# GNSS_B.net
KiCad netlist of a schematic drawn in Altium Designer
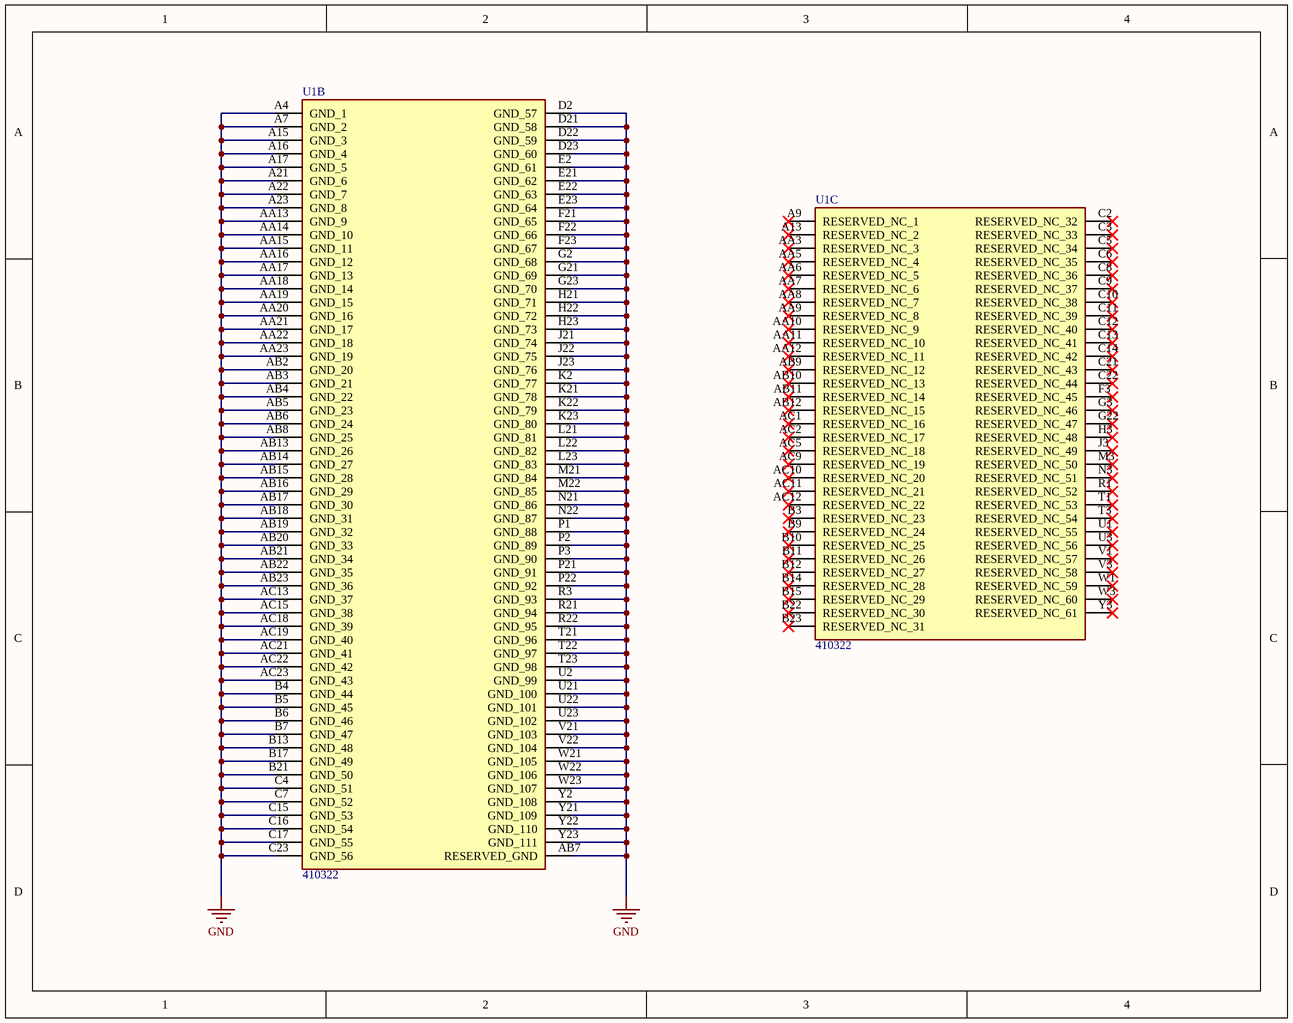
[diagram p0: GNSS_B.SchDoc]

(export (version "E")
  (design (tool "Eeschema 10.0.6"))
  (components
    (comp (ref "U1")
      (value "410322")
      (footprint "LGA239C127P23X23_3100X3100X417N")
      (description "mosaicâ„¢-X5 RF Receiver BeiDou, Galileo, GLONASS, GNSS, GPS")
      (fields (field (name "MF") "Septentrio Inc."))
      (libsource (lib "410322") (part "410322"))
    )
  )
  (nets
    (net (code "1") (name "GND") (class "Default")
      (node (ref "U1") (pin "A15") (pinfunction "GND_3_A15") (pintype "power_in"))
      (node (ref "U1") (pin "A16") (pinfunction "GND_4_A16") (pintype "power_in"))
      (node (ref "U1") (pin "A17") (pinfunction "GND_5_A17") (pintype "power_in"))
      (node (ref "U1") (pin "A21") (pinfunction "GND_6_A21") (pintype "power_in"))
      (node (ref "U1") (pin "A22") (pinfunction "GND_7_A22") (pintype "power_in"))
      (node (ref "U1") (pin "A23") (pinfunction "GND_8_A23") (pintype "power_in"))
      (node (ref "U1") (pin "A4") (pinfunction "GND_1_A4") (pintype "power_in"))
      (node (ref "U1") (pin "A7") (pinfunction "GND_2_A7") (pintype "power_in"))
      (node (ref "U1") (pin "AA13") (pinfunction "GND_9_AA13") (pintype "power_in"))
      (node (ref "U1") (pin "AA14") (pinfunction "GND_10_AA14") (pintype "power_in"))
      (node (ref "U1") (pin "AA15") (pinfunction "GND_11_AA15") (pintype "power_in"))
      (node (ref "U1") (pin "AA16") (pinfunction "GND_12_AA16") (pintype "power_in"))
      (node (ref "U1") (pin "AA17") (pinfunction "GND_13_AA17") (pintype "power_in"))
      (node (ref "U1") (pin "AA18") (pinfunction "GND_14_AA18") (pintype "power_in"))
      (node (ref "U1") (pin "AA19") (pinfunction "GND_15_AA19") (pintype "power_in"))
      (node (ref "U1") (pin "AA20") (pinfunction "GND_16_AA20") (pintype "power_in"))
      (node (ref "U1") (pin "AA21") (pinfunction "GND_17_AA21") (pintype "power_in"))
      (node (ref "U1") (pin "AA22") (pinfunction "GND_18_AA22") (pintype "power_in"))
      (node (ref "U1") (pin "AA23") (pinfunction "GND_19_AA23") (pintype "power_in"))
      (node (ref "U1") (pin "AB13") (pinfunction "GND_26_AB13") (pintype "power_in"))
      (node (ref "U1") (pin "AB14") (pinfunction "GND_27_AB14") (pintype "power_in"))
      (node (ref "U1") (pin "AB15") (pinfunction "GND_28_AB15") (pintype "power_in"))
      (node (ref "U1") (pin "AB16") (pinfunction "GND_29_AB16") (pintype "power_in"))
      (node (ref "U1") (pin "AB17") (pinfunction "GND_30_AB17") (pintype "power_in"))
      (node (ref "U1") (pin "AB18") (pinfunction "GND_31_AB18") (pintype "power_in"))
      (node (ref "U1") (pin "AB19") (pinfunction "GND_32_AB19") (pintype "power_in"))
      (node (ref "U1") (pin "AB2") (pinfunction "GND_20_AB2") (pintype "power_in"))
      (node (ref "U1") (pin "AB20") (pinfunction "GND_33_AB20") (pintype "power_in"))
      (node (ref "U1") (pin "AB21") (pinfunction "GND_34_AB21") (pintype "power_in"))
      (node (ref "U1") (pin "AB22") (pinfunction "GND_35_AB22") (pintype "power_in"))
      (node (ref "U1") (pin "AB23") (pinfunction "GND_36_AB23") (pintype "power_in"))
      (node (ref "U1") (pin "AB3") (pinfunction "GND_21_AB3") (pintype "power_in"))
      (node (ref "U1") (pin "AB4") (pinfunction "GND_22_AB4") (pintype "power_in"))
      (node (ref "U1") (pin "AB5") (pinfunction "GND_23_AB5") (pintype "power_in"))
      (node (ref "U1") (pin "AB6") (pinfunction "GND_24_AB6") (pintype "power_in"))
      (node (ref "U1") (pin "AB7") (pinfunction "RESERVED_GND_AB7") (pintype "passive"))
      (node (ref "U1") (pin "AB8") (pinfunction "GND_25_AB8") (pintype "power_in"))
      (node (ref "U1") (pin "AC13") (pinfunction "GND_37_AC13") (pintype "power_in"))
      (node (ref "U1") (pin "AC15") (pinfunction "GND_38_AC15") (pintype "power_in"))
      (node (ref "U1") (pin "AC18") (pinfunction "GND_39_AC18") (pintype "power_in"))
      (node (ref "U1") (pin "AC19") (pinfunction "GND_40_AC19") (pintype "power_in"))
      (node (ref "U1") (pin "AC21") (pinfunction "GND_41_AC21") (pintype "power_in"))
      (node (ref "U1") (pin "AC22") (pinfunction "GND_42_AC22") (pintype "power_in"))
      (node (ref "U1") (pin "AC23") (pinfunction "GND_43_AC23") (pintype "power_in"))
      (node (ref "U1") (pin "B13") (pinfunction "GND_48_B13") (pintype "power_in"))
      (node (ref "U1") (pin "B17") (pinfunction "GND_49_B17") (pintype "power_in"))
      (node (ref "U1") (pin "B21") (pinfunction "GND_50_B21") (pintype "power_in"))
      (node (ref "U1") (pin "B4") (pinfunction "GND_44_B4") (pintype "power_in"))
      (node (ref "U1") (pin "B5") (pinfunction "GND_45_B5") (pintype "power_in"))
      (node (ref "U1") (pin "B6") (pinfunction "GND_46_B6") (pintype "power_in"))
      (node (ref "U1") (pin "B7") (pinfunction "GND_47_B7") (pintype "power_in"))
      (node (ref "U1") (pin "C15") (pinfunction "GND_53_C15") (pintype "power_in"))
      (node (ref "U1") (pin "C16") (pinfunction "GND_54_C16") (pintype "power_in"))
      (node (ref "U1") (pin "C17") (pinfunction "GND_55_C17") (pintype "power_in"))
      (node (ref "U1") (pin "C23") (pinfunction "GND_56_C23") (pintype "power_in"))
      (node (ref "U1") (pin "C4") (pinfunction "GND_51_C4") (pintype "power_in"))
      (node (ref "U1") (pin "C7") (pinfunction "GND_52_C7") (pintype "power_in"))
      (node (ref "U1") (pin "D2") (pinfunction "GND_57_D2") (pintype "power_in"))
      (node (ref "U1") (pin "D21") (pinfunction "GND_58_D21") (pintype "power_in"))
      (node (ref "U1") (pin "D22") (pinfunction "GND_59_D22") (pintype "power_in"))
      (node (ref "U1") (pin "D23") (pinfunction "GND_60_D23") (pintype "power_in"))
      (node (ref "U1") (pin "E2") (pinfunction "GND_61_E2") (pintype "power_in"))
      (node (ref "U1") (pin "E21") (pinfunction "GND_62_E21") (pintype "power_in"))
      (node (ref "U1") (pin "E22") (pinfunction "GND_63_E22") (pintype "power_in"))
      (node (ref "U1") (pin "E23") (pinfunction "GND_64_E23") (pintype "power_in"))
      (node (ref "U1") (pin "F21") (pinfunction "GND_65_F21") (pintype "power_in"))
      (node (ref "U1") (pin "F22") (pinfunction "GND_66_F22") (pintype "power_in"))
      (node (ref "U1") (pin "F23") (pinfunction "GND_67_F23") (pintype "power_in"))
      (node (ref "U1") (pin "G2") (pinfunction "GND_68_G2") (pintype "power_in"))
      (node (ref "U1") (pin "G21") (pinfunction "GND_69_G21") (pintype "power_in"))
      (node (ref "U1") (pin "G23") (pinfunction "GND_70_G23") (pintype "power_in"))
      (node (ref "U1") (pin "H21") (pinfunction "GND_71_H21") (pintype "power_in"))
      (node (ref "U1") (pin "H22") (pinfunction "GND_72_H22") (pintype "power_in"))
      (node (ref "U1") (pin "H23") (pinfunction "GND_73_H23") (pintype "power_in"))
      (node (ref "U1") (pin "J21") (pinfunction "GND_74_J21") (pintype "power_in"))
      (node (ref "U1") (pin "J22") (pinfunction "GND_75_J22") (pintype "power_in"))
      (node (ref "U1") (pin "J23") (pinfunction "GND_76_J23") (pintype "power_in"))
      (node (ref "U1") (pin "K2") (pinfunction "GND_77_K2") (pintype "power_in"))
      (node (ref "U1") (pin "K21") (pinfunction "GND_78_K21") (pintype "power_in"))
      (node (ref "U1") (pin "K22") (pinfunction "GND_79_K22") (pintype "power_in"))
      (node (ref "U1") (pin "K23") (pinfunction "GND_80_K23") (pintype "power_in"))
      (node (ref "U1") (pin "L21") (pinfunction "GND_81_L21") (pintype "power_in"))
      (node (ref "U1") (pin "L22") (pinfunction "GND_82_L22") (pintype "power_in"))
      (node (ref "U1") (pin "L23") (pinfunction "GND_83_L23") (pintype "power_in"))
      (node (ref "U1") (pin "M21") (pinfunction "GND_84_M21") (pintype "power_in"))
      (node (ref "U1") (pin "M22") (pinfunction "GND_85_M22") (pintype "power_in"))
      (node (ref "U1") (pin "N21") (pinfunction "GND_86_N21") (pintype "power_in"))
      (node (ref "U1") (pin "N22") (pinfunction "GND_87_N22") (pintype "power_in"))
      (node (ref "U1") (pin "P1") (pinfunction "GND_88_P1") (pintype "power_in"))
      (node (ref "U1") (pin "P2") (pinfunction "GND_89_P2") (pintype "power_in"))
      (node (ref "U1") (pin "P21") (pinfunction "GND_91_P21") (pintype "power_in"))
      (node (ref "U1") (pin "P22") (pinfunction "GND_92_P22") (pintype "power_in"))
      (node (ref "U1") (pin "P3") (pinfunction "GND_90_P3") (pintype "power_in"))
      (node (ref "U1") (pin "R21") (pinfunction "GND_94_R21") (pintype "power_in"))
      (node (ref "U1") (pin "R22") (pinfunction "GND_95_R22") (pintype "power_in"))
      (node (ref "U1") (pin "R3") (pinfunction "GND_93_R3") (pintype "power_in"))
      (node (ref "U1") (pin "T21") (pinfunction "GND_96_T21") (pintype "power_in"))
      (node (ref "U1") (pin "T22") (pinfunction "GND_97_T22") (pintype "power_in"))
      (node (ref "U1") (pin "T23") (pinfunction "GND_98_T23") (pintype "power_in"))
      (node (ref "U1") (pin "U2") (pinfunction "GND_99_U2") (pintype "power_in"))
      (node (ref "U1") (pin "U21") (pinfunction "GND_100_U21") (pintype "power_in"))
      (node (ref "U1") (pin "U22") (pinfunction "GND_101_U22") (pintype "power_in"))
      (node (ref "U1") (pin "U23") (pinfunction "GND_102_U23") (pintype "power_in"))
      (node (ref "U1") (pin "V21") (pinfunction "GND_103_V21") (pintype "power_in"))
      (node (ref "U1") (pin "V22") (pinfunction "GND_104_V22") (pintype "power_in"))
      (node (ref "U1") (pin "W21") (pinfunction "GND_105_W21") (pintype "power_in"))
      (node (ref "U1") (pin "W22") (pinfunction "GND_106_W22") (pintype "power_in"))
      (node (ref "U1") (pin "W23") (pinfunction "GND_107_W23") (pintype "power_in"))
      (node (ref "U1") (pin "Y2") (pinfunction "GND_108_Y2") (pintype "power_in"))
      (node (ref "U1") (pin "Y21") (pinfunction "GND_109_Y21") (pintype "power_in"))
      (node (ref "U1") (pin "Y22") (pinfunction "GND_110_Y22") (pintype "power_in"))
      (node (ref "U1") (pin "Y23") (pinfunction "GND_111_Y23") (pintype "power_in"))
    )
    (net (code "2") (name "unconnected-(U1C-RESERVED_NC_1-PadA9)") (class "Default")
      (node (ref "U1") (pin "A9") (pinfunction "RESERVED_NC_1_A9") (pintype "passive+no_connect"))
    )
    (net (code "3") (name "unconnected-(U1C-RESERVED_NC_2-PadA13)") (class "Default")
      (node (ref "U1") (pin "A13") (pinfunction "RESERVED_NC_2_A13") (pintype "passive+no_connect"))
    )
    (net (code "4") (name "unconnected-(U1C-RESERVED_NC_3-PadAA3)") (class "Default")
      (node (ref "U1") (pin "AA3") (pinfunction "RESERVED_NC_3_AA3") (pintype "passive+no_connect"))
    )
    (net (code "5") (name "unconnected-(U1C-RESERVED_NC_4-PadAA5)") (class "Default")
      (node (ref "U1") (pin "AA5") (pinfunction "RESERVED_NC_4_AA5") (pintype "passive+no_connect"))
    )
    (net (code "6") (name "unconnected-(U1C-RESERVED_NC_5-PadAA6)") (class "Default")
      (node (ref "U1") (pin "AA6") (pinfunction "RESERVED_NC_5_AA6") (pintype "passive+no_connect"))
    )
    (net (code "7") (name "unconnected-(U1C-RESERVED_NC_6-PadAA7)") (class "Default")
      (node (ref "U1") (pin "AA7") (pinfunction "RESERVED_NC_6_AA7") (pintype "passive+no_connect"))
    )
    (net (code "8") (name "unconnected-(U1C-RESERVED_NC_7-PadAA8)") (class "Default")
      (node (ref "U1") (pin "AA8") (pinfunction "RESERVED_NC_7_AA8") (pintype "passive+no_connect"))
    )
    (net (code "9") (name "unconnected-(U1C-RESERVED_NC_8-PadAA9)") (class "Default")
      (node (ref "U1") (pin "AA9") (pinfunction "RESERVED_NC_8_AA9") (pintype "passive+no_connect"))
    )
    (net (code "10") (name "unconnected-(U1C-RESERVED_NC_9-PadAA10)") (class "Default")
      (node (ref "U1") (pin "AA10") (pinfunction "RESERVED_NC_9_AA10") (pintype "passive+no_connect"))
    )
    (net (code "11") (name "unconnected-(U1C-RESERVED_NC_10-PadAA11)") (class "Default")
      (node (ref "U1") (pin "AA11") (pinfunction "RESERVED_NC_10_AA11") (pintype "passive+no_connect"))
    )
    (net (code "12") (name "unconnected-(U1C-RESERVED_NC_11-PadAA12)") (class "Default")
      (node (ref "U1") (pin "AA12") (pinfunction "RESERVED_NC_11_AA12") (pintype "passive+no_connect"))
    )
    (net (code "13") (name "unconnected-(U1C-RESERVED_NC_12-PadAB9)") (class "Default")
      (node (ref "U1") (pin "AB9") (pinfunction "RESERVED_NC_12_AB9") (pintype "passive+no_connect"))
    )
    (net (code "14") (name "unconnected-(U1C-RESERVED_NC_13-PadAB10)") (class "Default")
      (node (ref "U1") (pin "AB10") (pinfunction "RESERVED_NC_13_AB10") (pintype "passive+no_connect"))
    )
    (net (code "15") (name "unconnected-(U1C-RESERVED_NC_14-PadAB11)") (class "Default")
      (node (ref "U1") (pin "AB11") (pinfunction "RESERVED_NC_14_AB11") (pintype "passive+no_connect"))
    )
    (net (code "16") (name "unconnected-(U1C-RESERVED_NC_15-PadAB12)") (class "Default")
      (node (ref "U1") (pin "AB12") (pinfunction "RESERVED_NC_15_AB12") (pintype "passive+no_connect"))
    )
    (net (code "17") (name "unconnected-(U1C-RESERVED_NC_16-PadAC1)") (class "Default")
      (node (ref "U1") (pin "AC1") (pinfunction "RESERVED_NC_16_AC1") (pintype "passive+no_connect"))
    )
    (net (code "18") (name "unconnected-(U1C-RESERVED_NC_17-PadAC2)") (class "Default")
      (node (ref "U1") (pin "AC2") (pinfunction "RESERVED_NC_17_AC2") (pintype "passive+no_connect"))
    )
    (net (code "19") (name "unconnected-(U1C-RESERVED_NC_18-PadAC5)") (class "Default")
      (node (ref "U1") (pin "AC5") (pinfunction "RESERVED_NC_18_AC5") (pintype "passive+no_connect"))
    )
    (net (code "20") (name "unconnected-(U1C-RESERVED_NC_19-PadAC9)") (class "Default")
      (node (ref "U1") (pin "AC9") (pinfunction "RESERVED_NC_19_AC9") (pintype "passive+no_connect"))
    )
    (net (code "21") (name "unconnected-(U1C-RESERVED_NC_20-PadAC10)") (class "Default")
      (node (ref "U1") (pin "AC10") (pinfunction "RESERVED_NC_20_AC10") (pintype "passive+no_connect"))
    )
    (net (code "22") (name "unconnected-(U1C-RESERVED_NC_21-PadAC11)") (class "Default")
      (node (ref "U1") (pin "AC11") (pinfunction "RESERVED_NC_21_AC11") (pintype "passive+no_connect"))
    )
    (net (code "23") (name "unconnected-(U1C-RESERVED_NC_22-PadAC12)") (class "Default")
      (node (ref "U1") (pin "AC12") (pinfunction "RESERVED_NC_22_AC12") (pintype "passive+no_connect"))
    )
    (net (code "24") (name "unconnected-(U1C-RESERVED_NC_23-PadB3)") (class "Default")
      (node (ref "U1") (pin "B3") (pinfunction "RESERVED_NC_23_B3") (pintype "passive+no_connect"))
    )
    (net (code "25") (name "unconnected-(U1C-RESERVED_NC_24-PadB9)") (class "Default")
      (node (ref "U1") (pin "B9") (pinfunction "RESERVED_NC_24_B9") (pintype "passive+no_connect"))
    )
    (net (code "26") (name "unconnected-(U1C-RESERVED_NC_25-PadB10)") (class "Default")
      (node (ref "U1") (pin "B10") (pinfunction "RESERVED_NC_25_B10") (pintype "passive+no_connect"))
    )
    (net (code "27") (name "unconnected-(U1C-RESERVED_NC_26-PadB11)") (class "Default")
      (node (ref "U1") (pin "B11") (pinfunction "RESERVED_NC_26_B11") (pintype "passive+no_connect"))
    )
    (net (code "28") (name "unconnected-(U1C-RESERVED_NC_27-PadB12)") (class "Default")
      (node (ref "U1") (pin "B12") (pinfunction "RESERVED_NC_27_B12") (pintype "passive+no_connect"))
    )
    (net (code "29") (name "unconnected-(U1C-RESERVED_NC_28-PadB14)") (class "Default")
      (node (ref "U1") (pin "B14") (pinfunction "RESERVED_NC_28_B14") (pintype "passive+no_connect"))
    )
    (net (code "30") (name "unconnected-(U1C-RESERVED_NC_29-PadB15)") (class "Default")
      (node (ref "U1") (pin "B15") (pinfunction "RESERVED_NC_29_B15") (pintype "passive+no_connect"))
    )
    (net (code "31") (name "unconnected-(U1C-RESERVED_NC_30-PadB22)") (class "Default")
      (node (ref "U1") (pin "B22") (pinfunction "RESERVED_NC_30_B22") (pintype "passive+no_connect"))
    )
    (net (code "32") (name "unconnected-(U1C-RESERVED_NC_31-PadB23)") (class "Default")
      (node (ref "U1") (pin "B23") (pinfunction "RESERVED_NC_31_B23") (pintype "passive+no_connect"))
    )
    (net (code "33") (name "unconnected-(U1C-RESERVED_NC_32-PadC2)") (class "Default")
      (node (ref "U1") (pin "C2") (pinfunction "RESERVED_NC_32_C2") (pintype "passive+no_connect"))
    )
    (net (code "34") (name "unconnected-(U1C-RESERVED_NC_33-PadC3)") (class "Default")
      (node (ref "U1") (pin "C3") (pinfunction "RESERVED_NC_33_C3") (pintype "passive+no_connect"))
    )
    (net (code "35") (name "unconnected-(U1C-RESERVED_NC_34-PadC5)") (class "Default")
      (node (ref "U1") (pin "C5") (pinfunction "RESERVED_NC_34_C5") (pintype "passive+no_connect"))
    )
    (net (code "36") (name "unconnected-(U1C-RESERVED_NC_35-PadC6)") (class "Default")
      (node (ref "U1") (pin "C6") (pinfunction "RESERVED_NC_35_C6") (pintype "passive+no_connect"))
    )
    (net (code "37") (name "unconnected-(U1C-RESERVED_NC_36-PadC8)") (class "Default")
      (node (ref "U1") (pin "C8") (pinfunction "RESERVED_NC_36_C8") (pintype "passive+no_connect"))
    )
    (net (code "38") (name "unconnected-(U1C-RESERVED_NC_37-PadC9)") (class "Default")
      (node (ref "U1") (pin "C9") (pinfunction "RESERVED_NC_37_C9") (pintype "passive+no_connect"))
    )
    (net (code "39") (name "unconnected-(U1C-RESERVED_NC_38-PadC10)") (class "Default")
      (node (ref "U1") (pin "C10") (pinfunction "RESERVED_NC_38_C10") (pintype "passive+no_connect"))
    )
    (net (code "40") (name "unconnected-(U1C-RESERVED_NC_39-PadC11)") (class "Default")
      (node (ref "U1") (pin "C11") (pinfunction "RESERVED_NC_39_C11") (pintype "passive+no_connect"))
    )
    (net (code "41") (name "unconnected-(U1C-RESERVED_NC_40-PadC12)") (class "Default")
      (node (ref "U1") (pin "C12") (pinfunction "RESERVED_NC_40_C12") (pintype "passive+no_connect"))
    )
    (net (code "42") (name "unconnected-(U1C-RESERVED_NC_41-PadC13)") (class "Default")
      (node (ref "U1") (pin "C13") (pinfunction "RESERVED_NC_41_C13") (pintype "passive+no_connect"))
    )
    (net (code "43") (name "unconnected-(U1C-RESERVED_NC_42-PadC14)") (class "Default")
      (node (ref "U1") (pin "C14") (pinfunction "RESERVED_NC_42_C14") (pintype "passive+no_connect"))
    )
    (net (code "44") (name "unconnected-(U1C-RESERVED_NC_43-PadC21)") (class "Default")
      (node (ref "U1") (pin "C21") (pinfunction "RESERVED_NC_43_C21") (pintype "passive+no_connect"))
    )
    (net (code "45") (name "unconnected-(U1C-RESERVED_NC_44-PadC22)") (class "Default")
      (node (ref "U1") (pin "C22") (pinfunction "RESERVED_NC_44_C22") (pintype "passive+no_connect"))
    )
    (net (code "46") (name "unconnected-(U1C-RESERVED_NC_45-PadF3)") (class "Default")
      (node (ref "U1") (pin "F3") (pinfunction "RESERVED_NC_45_F3") (pintype "passive+no_connect"))
    )
    (net (code "47") (name "unconnected-(U1C-RESERVED_NC_46-PadG3)") (class "Default")
      (node (ref "U1") (pin "G3") (pinfunction "RESERVED_NC_46_G3") (pintype "passive+no_connect"))
    )
    (net (code "48") (name "unconnected-(U1C-RESERVED_NC_47-PadG22)") (class "Default")
      (node (ref "U1") (pin "G22") (pinfunction "RESERVED_NC_47_G22") (pintype "passive+no_connect"))
    )
    (net (code "49") (name "unconnected-(U1C-RESERVED_NC_48-PadH3)") (class "Default")
      (node (ref "U1") (pin "H3") (pinfunction "RESERVED_NC_48_H3") (pintype "passive+no_connect"))
    )
    (net (code "50") (name "unconnected-(U1C-RESERVED_NC_49-PadJ3)") (class "Default")
      (node (ref "U1") (pin "J3") (pinfunction "RESERVED_NC_49_J3") (pintype "passive+no_connect"))
    )
    (net (code "51") (name "unconnected-(U1C-RESERVED_NC_50-PadM3)") (class "Default")
      (node (ref "U1") (pin "M3") (pinfunction "RESERVED_NC_50_M3") (pintype "passive+no_connect"))
    )
    (net (code "52") (name "unconnected-(U1C-RESERVED_NC_51-PadN3)") (class "Default")
      (node (ref "U1") (pin "N3") (pinfunction "RESERVED_NC_51_N3") (pintype "passive+no_connect"))
    )
    (net (code "53") (name "unconnected-(U1C-RESERVED_NC_52-PadR1)") (class "Default")
      (node (ref "U1") (pin "R1") (pinfunction "RESERVED_NC_52_R1") (pintype "passive+no_connect"))
    )
    (net (code "54") (name "unconnected-(U1C-RESERVED_NC_53-PadT1)") (class "Default")
      (node (ref "U1") (pin "T1") (pinfunction "RESERVED_NC_53_T1") (pintype "passive+no_connect"))
    )
    (net (code "55") (name "unconnected-(U1C-RESERVED_NC_54-PadT3)") (class "Default")
      (node (ref "U1") (pin "T3") (pinfunction "RESERVED_NC_54_T3") (pintype "passive+no_connect"))
    )
    (net (code "56") (name "unconnected-(U1C-RESERVED_NC_55-PadU1)") (class "Default")
      (node (ref "U1") (pin "U1") (pinfunction "RESERVED_NC_55_U1") (pintype "passive+no_connect"))
    )
    (net (code "57") (name "unconnected-(U1C-RESERVED_NC_56-PadU3)") (class "Default")
      (node (ref "U1") (pin "U3") (pinfunction "RESERVED_NC_56_U3") (pintype "passive+no_connect"))
    )
    (net (code "58") (name "unconnected-(U1C-RESERVED_NC_57-PadV1)") (class "Default")
      (node (ref "U1") (pin "V1") (pinfunction "RESERVED_NC_57_V1") (pintype "passive+no_connect"))
    )
    (net (code "59") (name "unconnected-(U1C-RESERVED_NC_58-PadV3)") (class "Default")
      (node (ref "U1") (pin "V3") (pinfunction "RESERVED_NC_58_V3") (pintype "passive+no_connect"))
    )
    (net (code "60") (name "unconnected-(U1C-RESERVED_NC_59-PadW1)") (class "Default")
      (node (ref "U1") (pin "W1") (pinfunction "RESERVED_NC_59_W1") (pintype "passive+no_connect"))
    )
    (net (code "61") (name "unconnected-(U1C-RESERVED_NC_60-PadW3)") (class "Default")
      (node (ref "U1") (pin "W3") (pinfunction "RESERVED_NC_60_W3") (pintype "passive+no_connect"))
    )
    (net (code "62") (name "unconnected-(U1C-RESERVED_NC_61-PadY3)") (class "Default")
      (node (ref "U1") (pin "Y3") (pinfunction "RESERVED_NC_61_Y3") (pintype "passive+no_connect"))
    )
  )
)
